# LEDResetBoardRevA.net
KiCad netlist of a schematic drawn in EAGLE
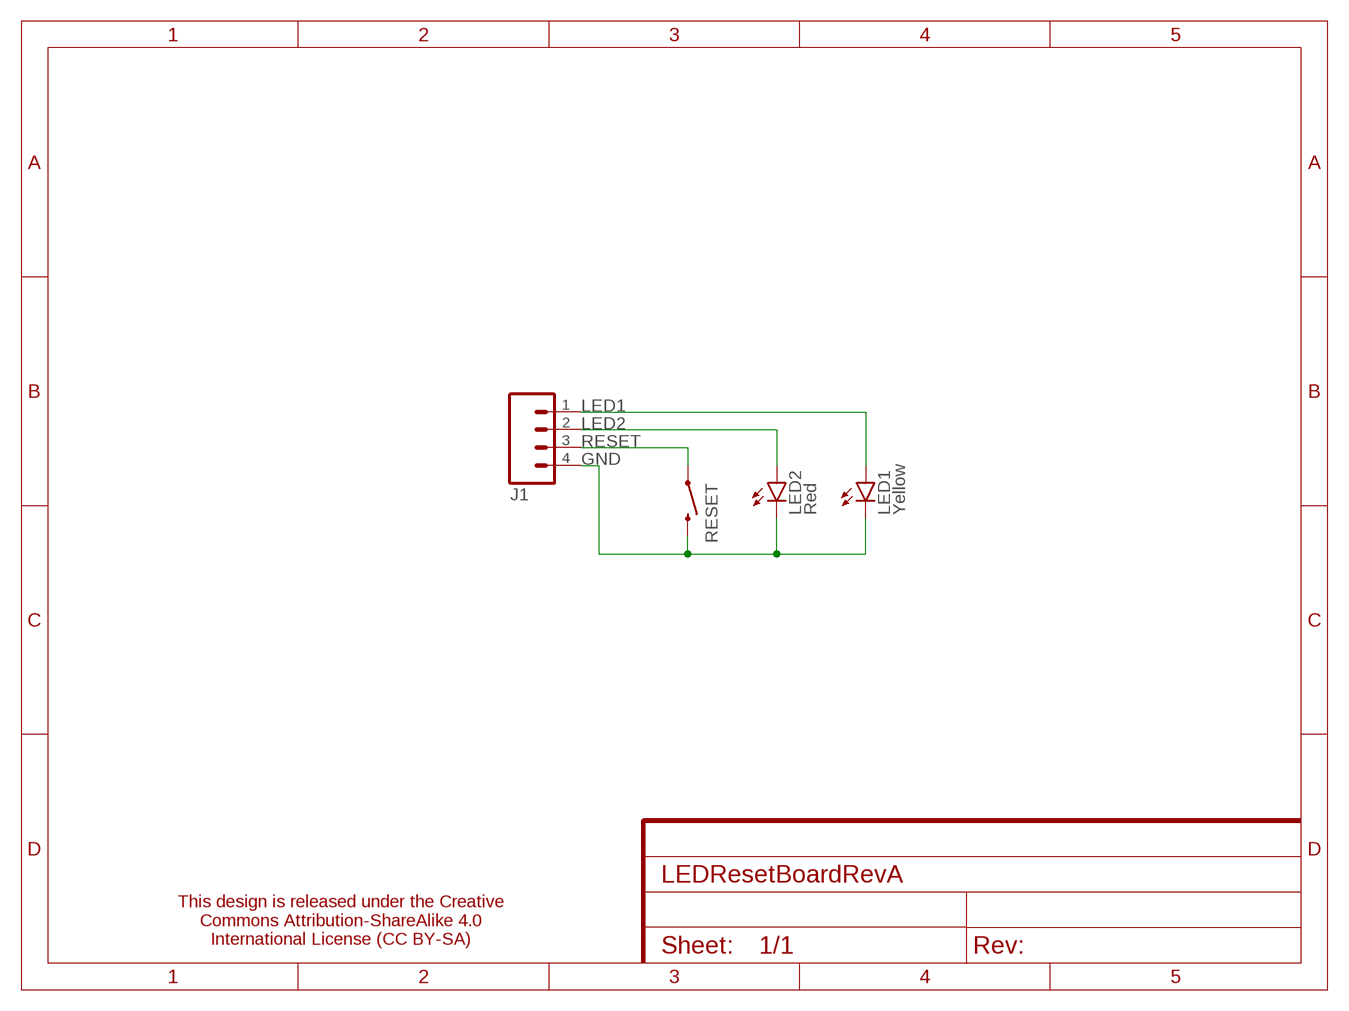
[diagram p0: schematic, sheet 1]

(export (version "E")
  (design (tool "Eeschema 10.0.6"))
  (components
    (comp (ref "J1")
      (value "M04PTH")
      (footprint "eagle-import:1X04")
      (libsource (lib "eagle-import") (part "M04PTH"))
    )
    (comp (ref "LED1")
      (value "Yellow")
      (footprint "eagle-import:LED3MM")
      (libsource (lib "eagle-import") (part "LED3MM"))
    )
    (comp (ref "LED2")
      (value "Red")
      (footprint "eagle-import:LED3MM")
      (libsource (lib "eagle-import") (part "LED3MM"))
    )
    (comp (ref "RESET")
      (value "SWITCH-MOMENTARY-2PTH")
      (footprint "eagle-import:TACTILE-PTH")
      (libsource (lib "eagle-import") (part "SWITCH-MOMENTARY-2PTH"))
    )
  )
  (nets
    (net (code "1") (name "/GND") (class "Default")
      (node (ref "J1") (pin "4") (pinfunction "4_4") (pintype "passive"))
      (node (ref "LED1") (pin "K") (pinfunction "C_K") (pintype "passive"))
      (node (ref "LED2") (pin "K") (pinfunction "C_K") (pintype "passive"))
      (node (ref "RESET") (pin "3") (pinfunction "2_3") (pintype "passive"))
    )
    (net (code "2") (name "/LED1") (class "Default")
      (node (ref "J1") (pin "1") (pinfunction "1_1") (pintype "passive"))
      (node (ref "LED1") (pin "A") (pinfunction "A_A") (pintype "passive"))
    )
    (net (code "3") (name "/LED2") (class "Default")
      (node (ref "J1") (pin "2") (pinfunction "2_2") (pintype "passive"))
      (node (ref "LED2") (pin "A") (pinfunction "A_A") (pintype "passive"))
    )
    (net (code "4") (name "/RESET") (class "Default")
      (node (ref "J1") (pin "3") (pinfunction "3_3") (pintype "passive"))
      (node (ref "RESET") (pin "1") (pinfunction "1_1") (pintype "passive"))
    )
  )
)
